# 4_15.net
KiCad netlist of a schematic drawn in EasyEDA
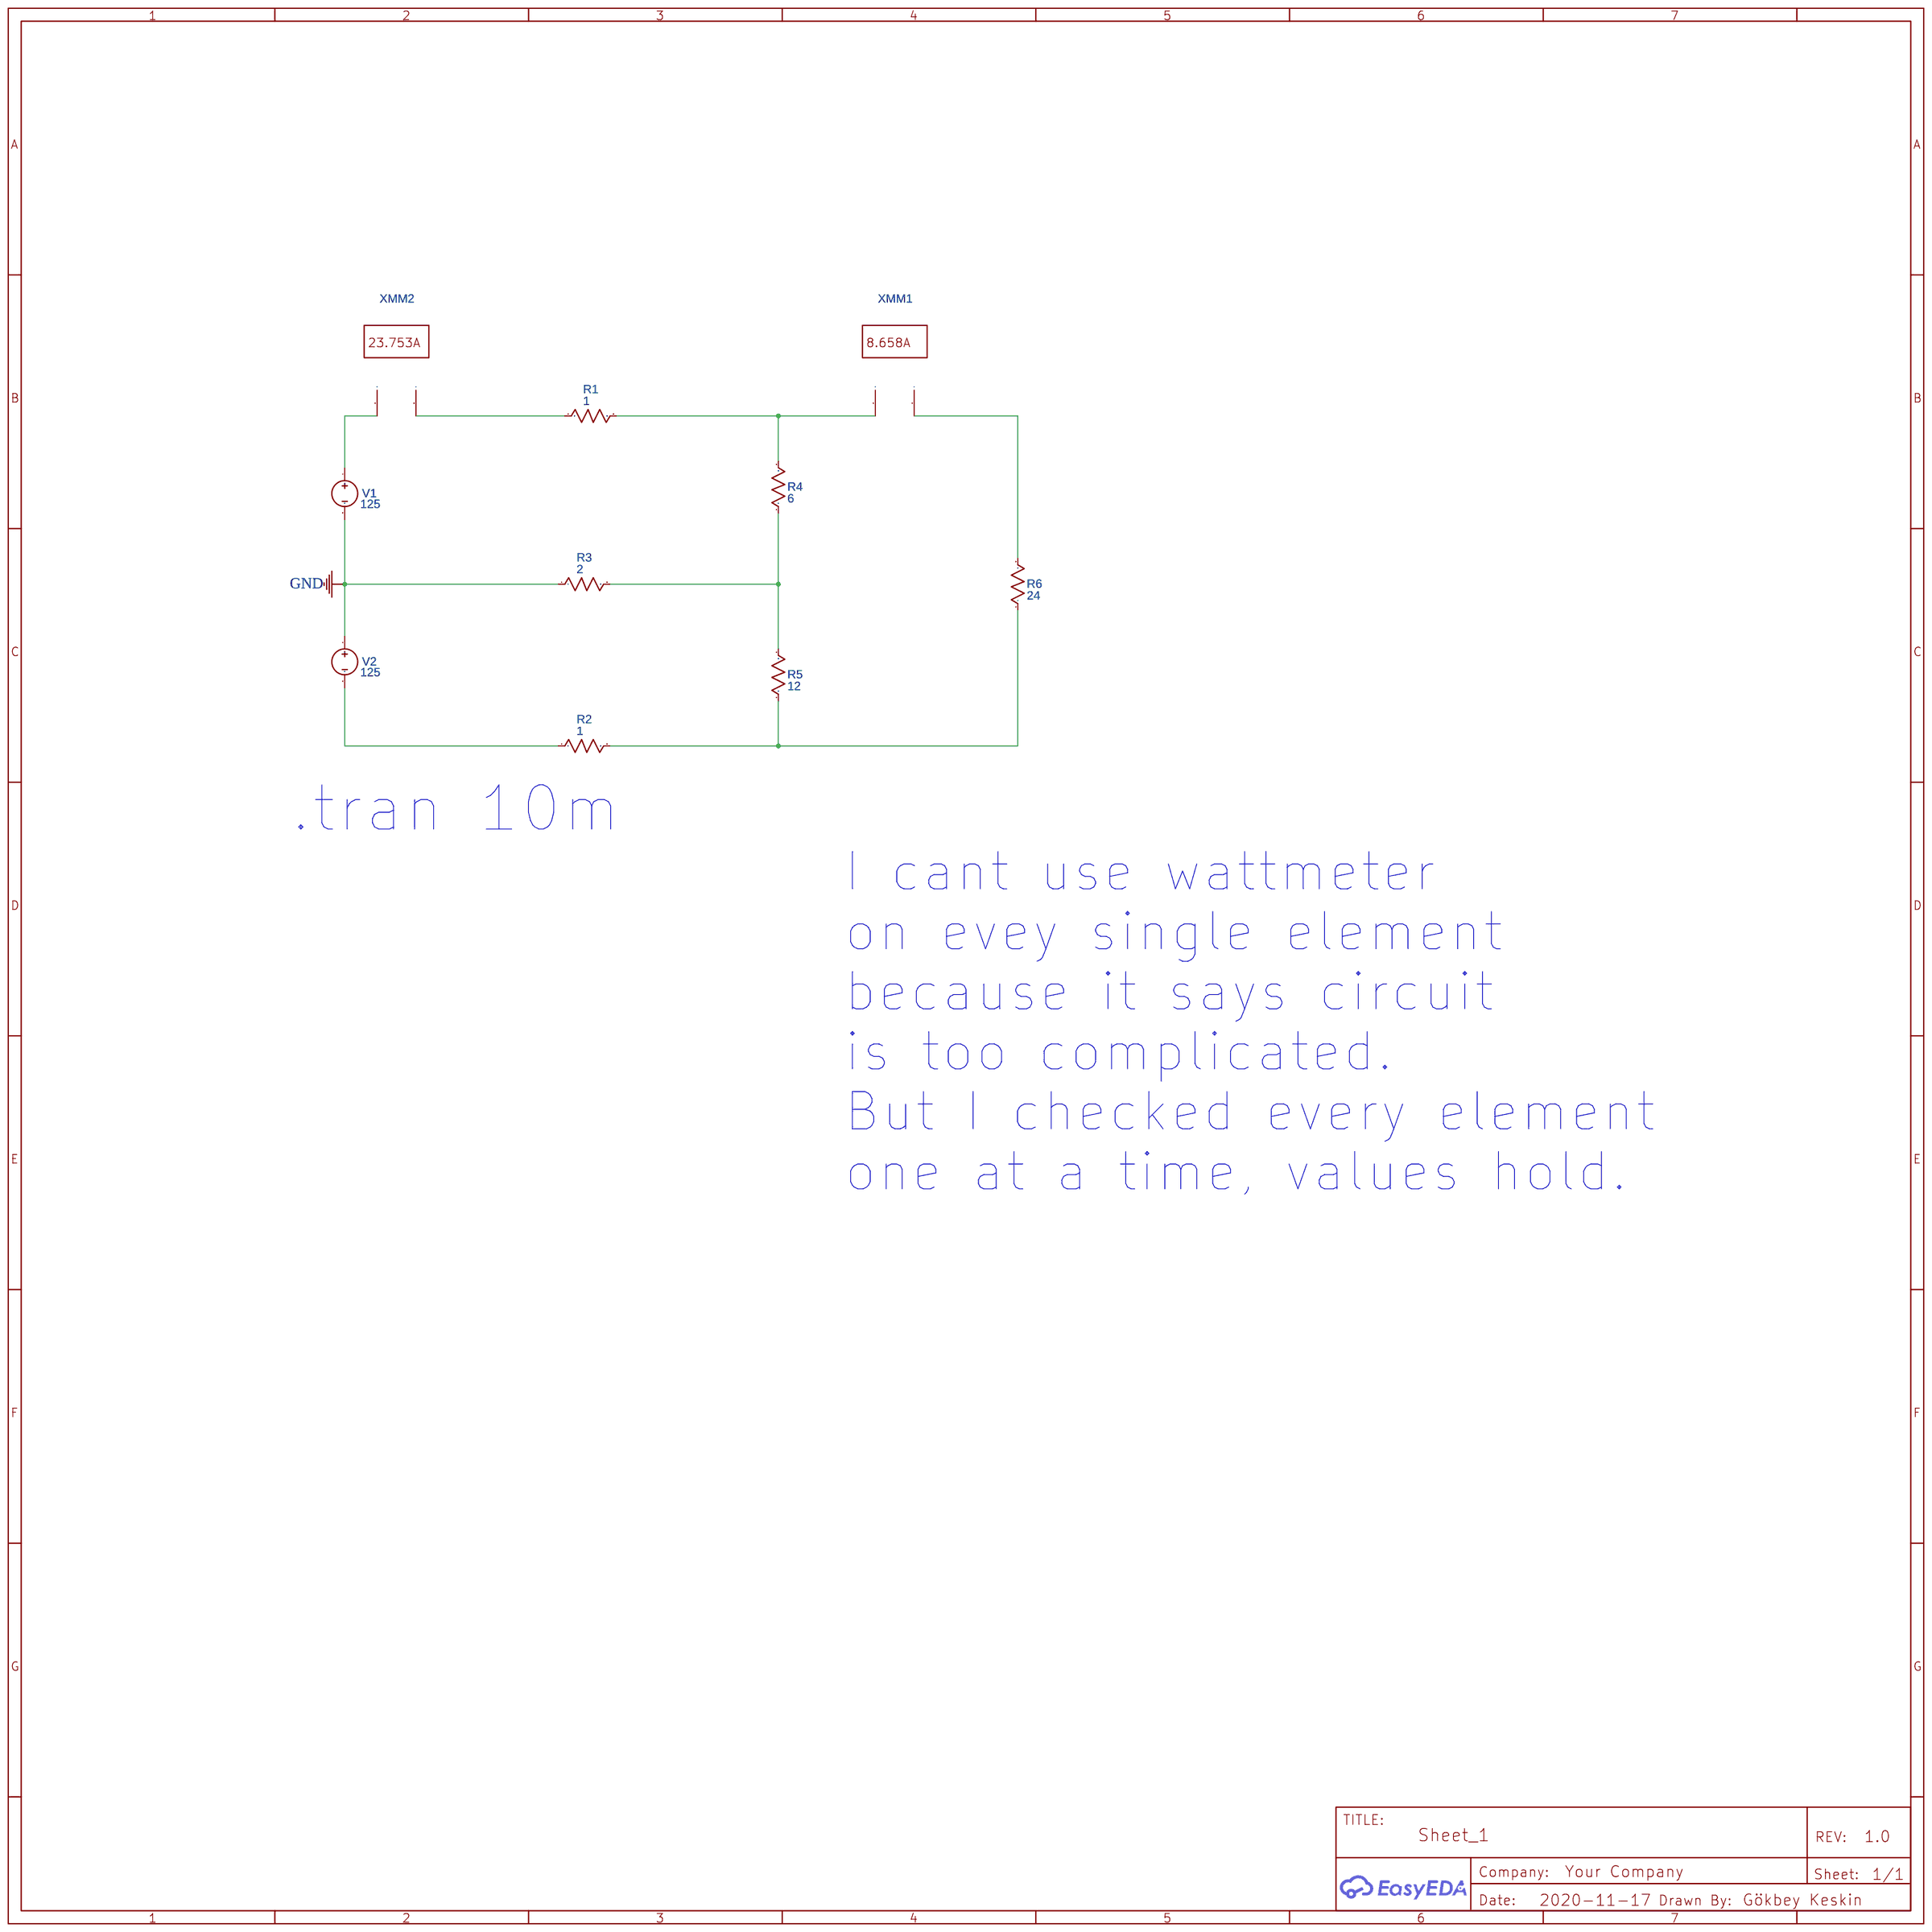
[diagram p0: schematic sheet]

(export (version "E")
  (design (tool "Eeschema 10.0.6"))
  (components
    (comp (ref "R1") (value "1") (libsource (lib "") (part "Resistor_US")))
    (comp (ref "R2") (value "1") (libsource (lib "") (part "Resistor_US")))
    (comp (ref "R3") (value "2") (libsource (lib "") (part "Resistor_US")))
    (comp (ref "R4") (value "6") (libsource (lib "") (part "Resistor_US_1")))
    (comp (ref "R5") (value "12") (libsource (lib "") (part "Resistor_US_1")))
    (comp (ref "R6") (value "24") (libsource (lib "") (part "Resistor_US_1")))
    (comp (ref "V1") (value "125") (libsource (lib "") (part "VDC")))
    (comp (ref "V2") (value "125") (libsource (lib "") (part "VDC")))
    (comp (ref "XMM1") (value "Multimeter") (libsource (lib "") (part "MULTIMETER")))
    (comp (ref "XMM2") (value "Multimeter") (libsource (lib "") (part "MULTIMETER_1")))
  )
  (nets
    (net (code "1") (name "GND") (class "Default")
      (node (ref "R3") (pin "1") (pinfunction "1_1") (pintype "unspecified"))
      (node (ref "V1") (pin "2") (pinfunction "2_2") (pintype "unspecified"))
      (node (ref "V2") (pin "1") (pinfunction "1_1") (pintype "unspecified"))
    )
    (net (code "2") (name "Net-(R2-Pad1)") (class "Default")
      (node (ref "R2") (pin "1") (pinfunction "1_1") (pintype "unspecified"))
      (node (ref "V2") (pin "2") (pinfunction "2_2") (pintype "unspecified"))
    )
    (net (code "3") (name "Net-(R2-Pad2)") (class "Default")
      (node (ref "R2") (pin "2") (pinfunction "2_2") (pintype "unspecified"))
      (node (ref "R5") (pin "1") (pinfunction "1_1") (pintype "unspecified"))
      (node (ref "R6") (pin "1") (pinfunction "1_1") (pintype "unspecified"))
    )
    (net (code "4") (name "Net-(R3-Pad2)") (class "Default")
      (node (ref "R3") (pin "2") (pinfunction "2_2") (pintype "unspecified"))
      (node (ref "R4") (pin "1") (pinfunction "1_1") (pintype "unspecified"))
      (node (ref "R5") (pin "2") (pinfunction "2_2") (pintype "unspecified"))
    )
    (net (code "5") (name "Net-(XMM1-+)") (class "Default")
      (node (ref "R1") (pin "2") (pinfunction "2_2") (pintype "unspecified"))
      (node (ref "R4") (pin "2") (pinfunction "2_2") (pintype "unspecified"))
      (node (ref "XMM1") (pin "1") (pinfunction "+_1") (pintype "unspecified"))
    )
    (net (code "6") (name "Net-(XMM1-I)") (class "Default")
      (node (ref "R6") (pin "2") (pinfunction "2_2") (pintype "unspecified"))
      (node (ref "XMM1") (pin "2") (pinfunction "I_2") (pintype "unspecified"))
    )
    (net (code "7") (name "Net-(XMM2-+)") (class "Default")
      (node (ref "V1") (pin "1") (pinfunction "1_1") (pintype "unspecified"))
      (node (ref "XMM2") (pin "1") (pinfunction "+_1") (pintype "unspecified"))
    )
    (net (code "8") (name "Net-(XMM2-I)") (class "Default")
      (node (ref "R1") (pin "1") (pinfunction "1_1") (pintype "unspecified"))
      (node (ref "XMM2") (pin "2") (pinfunction "I_2") (pintype "unspecified"))
    )
  )
)
